# ParteAnalogicaMedicion.net
KiCad netlist of a schematic drawn in Altium Designer
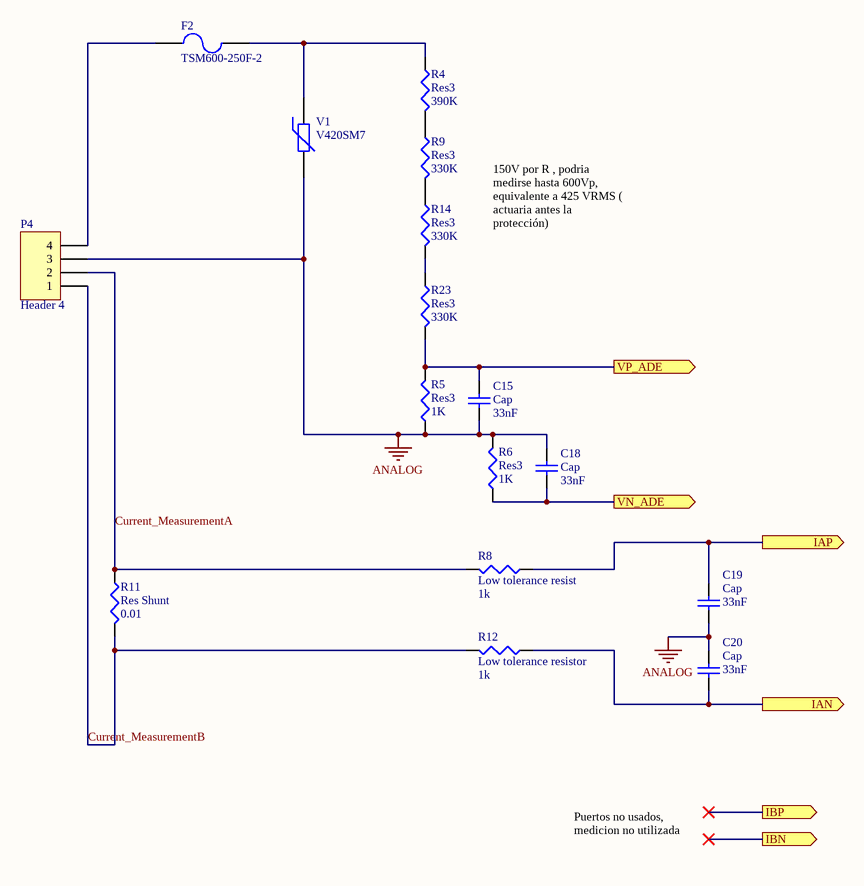
[diagram p0: ParteAnalogicaMedicion.SchDoc]

(export (version "E")
  (design (tool "Eeschema 10.0.6"))
  (components
    (comp (ref "C15")
      (value "Cap")
      (footprint "Custom0805")
      (description "Capacitor")
      (fields (field (name "ALTIUM_VALUE") "33nF") (field (name "PUBLISHER") "Altium Limited"))
      (libsource (lib "Miscellaneous Devices") (part "Cap"))
    )
    (comp (ref "C18")
      (value "Cap")
      (footprint "Custom0805")
      (description "Capacitor")
      (fields (field (name "ALTIUM_VALUE") "33nF") (field (name "PUBLISHER") "Altium Limited"))
      (libsource (lib "Miscellaneous Devices") (part "Cap"))
    )
    (comp (ref "C19")
      (value "Cap")
      (footprint "Custom0805")
      (description "Capacitor")
      (fields (field (name "ALTIUM_VALUE") "33nF") (field (name "PUBLISHER") "Altium Limited"))
      (libsource (lib "Miscellaneous Devices") (part "Cap"))
    )
    (comp (ref "C20")
      (value "Cap")
      (footprint "Custom0805")
      (description "Capacitor")
      (fields (field (name "ALTIUM_VALUE") "33nF") (field (name "PUBLISHER") "Altium Limited"))
      (libsource (lib "Miscellaneous Devices") (part "Cap"))
    )
    (comp (ref "F2")
      (value "TSM600-250F-2")
      (footprint "*SOIC254P1016X440-4N")
      (description "Fuse")
      (fields (field (name "PUBLISHER") "Altium Limited"))
      (libsource (lib "Miscellaneous Devices") (part "Fuse 2"))
    )
    (comp (ref "P4")
      (value "Header 4")
      (footprint "ConectorPrsr")
      (description "Header, 4-Pin")
      (fields (field (name "PUBLISHER") "Altium Limited"))
      (libsource (lib "Miscellaneous Connectors") (part "Header 4"))
    )
    (comp (ref "R4")
      (value "Res3")
      (footprint "Custom0805")
      (description "Resistor")
      (fields (field (name "ALTIUM_VALUE") "390K") (field (name "PUBLISHER") "Altium Limited"))
      (libsource (lib "Miscellaneous Devices") (part "Res3"))
    )
    (comp (ref "R5")
      (value "Res3")
      (footprint "Custom0805")
      (description "Resistor")
      (fields (field (name "ALTIUM_VALUE") "1K") (field (name "PUBLISHER") "Altium Limited"))
      (libsource (lib "Miscellaneous Devices") (part "Res3"))
    )
    (comp (ref "R6")
      (value "Res3")
      (footprint "Custom0805")
      (description "Resistor")
      (fields (field (name "ALTIUM_VALUE") "1K") (field (name "PUBLISHER") "Altium Limited"))
      (libsource (lib "Miscellaneous Devices") (part "Res3"))
    )
    (comp (ref "R8")
      (value "Low tolerance resist")
      (footprint "Custom0805")
      (description "Resistor")
      (fields (field (name "ALTIUM_VALUE") "1k") (field (name "PUBLISHER") "Altium Limited"))
      (libsource (lib "Miscellaneous Devices") (part "Res3"))
    )
    (comp (ref "R9")
      (value "Res3")
      (footprint "Custom0805")
      (description "Resistor")
      (fields (field (name "ALTIUM_VALUE") "330K") (field (name "PUBLISHER") "Altium Limited"))
      (libsource (lib "Miscellaneous Devices") (part "Res3"))
    )
    (comp (ref "R11")
      (value "Res Shunt")
      (footprint "RESC1000X525X52L180M")
      (description "Resistor")
      (fields (field (name "ALTIUM_VALUE") "0.01") (field (name "PUBLISHER") "Altium Limited"))
      (libsource (lib "Miscellaneous Devices") (part "Res3"))
    )
    (comp (ref "R12")
      (value "Low tolerance resistor")
      (footprint "Custom0805")
      (description "Resistor")
      (fields (field (name "ALTIUM_VALUE") "1k") (field (name "PUBLISHER") "Altium Limited"))
      (libsource (lib "Miscellaneous Devices") (part "Res3"))
    )
    (comp (ref "R14")
      (value "Res3")
      (footprint "Custom0805")
      (description "Resistor")
      (fields (field (name "ALTIUM_VALUE") "330K") (field (name "PUBLISHER") "Altium Limited"))
      (libsource (lib "Miscellaneous Devices") (part "Res3"))
    )
    (comp (ref "R23")
      (value "Res3")
      (footprint "C0805")
      (description "Resistor")
      (fields (field (name "ALTIUM_VALUE") "330K") (field (name "PUBLISHER") "Altium Limited"))
      (libsource (lib "Miscellaneous Devices") (part "Res3"))
    )
    (comp (ref "V1")
      (value "V420SM7")
      (footprint "PCBComponent_1")
      (description "Varistor (Voltage-Sensitive Resistor)")
      (fields (field (name "PUBLISHER") "Altium Limited"))
      (libsource (lib "Miscellaneous Devices") (part "Res Varistor"))
    )
  )
  (nets
    (net (code "1") (name "/Current_MeasurementA") (class "Default")
      (node (ref "P4") (pin "2") (pinfunction "2_2") (pintype "passive"))
      (node (ref "R11") (pin "1") (pinfunction "1_1") (pintype "passive"))
      (node (ref "R8") (pin "2") (pinfunction "2_2") (pintype "passive"))
    )
    (net (code "2") (name "/Current_MeasurementB") (class "Default")
      (node (ref "P4") (pin "1") (pinfunction "1_1") (pintype "passive"))
      (node (ref "R11") (pin "2") (pinfunction "2_2") (pintype "passive"))
      (node (ref "R12") (pin "2") (pinfunction "2_2") (pintype "passive"))
    )
    (net (code "3") (name "/IAN") (class "Default")
      (node (ref "C20") (pin "1") (pinfunction "1_1") (pintype "passive"))
      (node (ref "R12") (pin "1") (pinfunction "1_1") (pintype "passive"))
    )
    (net (code "4") (name "/IAP") (class "Default")
      (node (ref "C19") (pin "2") (pinfunction "2_2") (pintype "passive"))
      (node (ref "R8") (pin "1") (pinfunction "1_1") (pintype "passive"))
    )
    (net (code "7") (name "/VN_ADE") (class "Default")
      (node (ref "C18") (pin "1") (pinfunction "1_1") (pintype "passive"))
      (node (ref "R6") (pin "1") (pinfunction "1_1") (pintype "passive"))
    )
    (net (code "8") (name "/VP_ADE") (class "Default")
      (node (ref "C15") (pin "2") (pinfunction "2_2") (pintype "passive"))
      (node (ref "R23") (pin "2") (pinfunction "2_2") (pintype "passive"))
      (node (ref "R5") (pin "2") (pinfunction "2_2") (pintype "passive"))
    )
    (net (code "9") (name "ANALOG") (class "Default")
      (node (ref "C15") (pin "1") (pinfunction "1_1") (pintype "passive"))
      (node (ref "C18") (pin "2") (pinfunction "2_2") (pintype "passive"))
      (node (ref "C19") (pin "1") (pinfunction "1_1") (pintype "passive"))
      (node (ref "C20") (pin "2") (pinfunction "2_2") (pintype "passive"))
      (node (ref "P4") (pin "3") (pinfunction "3_3") (pintype "passive"))
      (node (ref "R5") (pin "1") (pinfunction "1_1") (pintype "passive"))
      (node (ref "R6") (pin "2") (pinfunction "2_2") (pintype "passive"))
      (node (ref "V1") (pin "2") (pinfunction "2_2") (pintype "passive"))
    )
    (net (code "10") (name "Net-(F2-Pad1)") (class "Default")
      (node (ref "F2") (pin "1") (pinfunction "1_1") (pintype "passive"))
      (node (ref "P4") (pin "4") (pinfunction "4_4") (pintype "passive"))
    )
    (net (code "11") (name "Net-(F2-Pad2)") (class "Default")
      (node (ref "F2") (pin "2") (pinfunction "2_2") (pintype "passive"))
      (node (ref "R4") (pin "1") (pinfunction "1_1") (pintype "passive"))
      (node (ref "V1") (pin "1") (pinfunction "1_1") (pintype "passive"))
    )
    (net (code "12") (name "Net-(R4-Pad2)") (class "Default")
      (node (ref "R4") (pin "2") (pinfunction "2_2") (pintype "passive"))
      (node (ref "R9") (pin "1") (pinfunction "1_1") (pintype "passive"))
    )
    (net (code "13") (name "Net-(R14-Pad1)") (class "Default")
      (node (ref "R14") (pin "1") (pinfunction "1_1") (pintype "passive"))
      (node (ref "R9") (pin "2") (pinfunction "2_2") (pintype "passive"))
    )
    (net (code "14") (name "Net-(R14-Pad2)") (class "Default")
      (node (ref "R14") (pin "2") (pinfunction "2_2") (pintype "passive"))
      (node (ref "R23") (pin "1") (pinfunction "1_1") (pintype "passive"))
    )
  )
)
